# 12V_Buck_Motor.net
KiCad netlist of a schematic drawn in Altium Designer
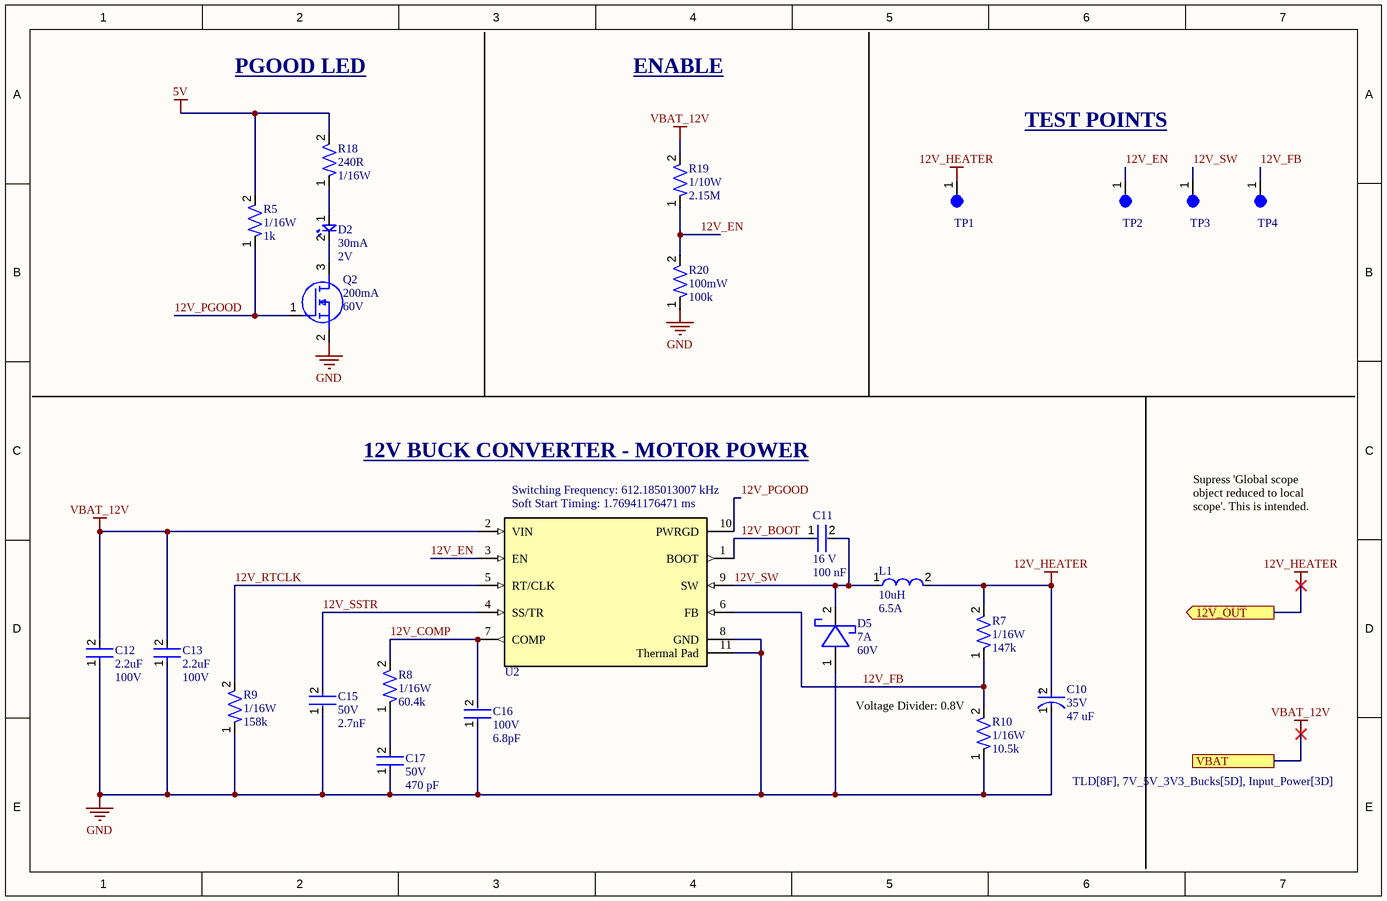
[diagram p0: 12V_Buck_Motor.SchDoc]

(export (version "E")
  (design (tool "Eeschema 10.0.6"))
  (components
    (comp (ref "C10")
      (value "EEH-ZC1V470P")
      (footprint "CAP-Radial-SMD")
      (description "CAP ALUM HYBRID 47UF 20% 35V SMD")
      (fields (field (name "VOLTAGE") "35V") (field (name "CAPACITANCE") "47 uF"))
      (libsource (lib "JLC_25") (part "CAP-47U-0002"))
    )
    (comp (ref "C11")
      (value "CC0402KRX7R7BB104")
      (footprint "CAP-0402")
      (description "CAP CER 0.1UF 16V X7R 0402")
      (fields (field (name "VOLTAGE RATING") "16 V") (field (name "CAPACITANCE") "100 nF"))
      (libsource (lib "JLC_25") (part "CAP-0.1U-0001"))
    )
    (comp (ref "C12")
      (value "CC1206KKX7R0BB225")
      (footprint "CAP-1206")
      (description "CAP CER 2.2UF 100V X7R 1206")
      (fields (field (name "CAPACITANCE") "2.2uF") (field (name "VOLTAGE") "100V"))
      (libsource (lib "JLC_25") (part "CAP-2.2U-0001"))
    )
    (comp (ref "C13")
      (value "CC1206KKX7R0BB225")
      (footprint "CAP-1206")
      (description "CAP CER 2.2UF 100V X7R 1206")
      (fields (field (name "CAPACITANCE") "2.2uF") (field (name "VOLTAGE") "100V"))
      (libsource (lib "JLC_25") (part "CAP-2.2U-0001"))
    )
    (comp (ref "C15")
      (value "GRM2165C1H272JA01D")
      (footprint "CAP-0805")
      (description "CAP CER 2700PF 50V C0G/NP0 0805")
      (fields (field (name "VOLTAGE") "50V") (field (name "CAPACITANCE") "2.7nF"))
      (libsource (lib "JLC_25") (part "CAP-2.7N-0001"))
    )
    (comp (ref "C16")
      (value "CC0603CRNPO0BN6R8")
      (footprint "CAP-0603")
      (description "CAP CER 6.8PF 100V C0G/NPO 0603")
      (fields (field (name "VOLTAGE") "100V") (field (name "CAPACITANCE") "6.8pF"))
      (libsource (lib "JLC_25") (part "CAP-6.8P-0001"))
    )
    (comp (ref "C17")
      (value "CC0805JRNPO9BN471")
      (footprint "CAP-0805")
      (description "CAP CER 470PF 50V C0G/NPO 0805")
      (fields (field (name "VOLTAGE") "50V") (field (name "CAPACITANCE") "470 pF"))
      (libsource (lib "JLC_25") (part "CAP-470P-0001"))
    )
    (comp (ref "D2")
      (value "BL-HKC36G-AV-TRB")
      (footprint "LED-0603")
      (description "LED YELLOW CLEAR 0603 SMD")
      (fields (field (name "FORWARD CURRENT") "30mA") (field (name "FORWARD VOLTAGE") "2V"))
      (libsource (lib "JLC_25") (part "LED-0001"))
    )
    (comp (ref "D5")
      (value "PDS760-13")
      (footprint "DO-POWERDI5")
      (description "DIODE SCHOTTKY 60V 7A POWERDI5")
      (fields (field (name "FORWARD CURRENT") "7A") (field (name "REVERSE VOLTAGE (DC)") "60V"))
      (libsource (lib "JLC_25") (part "DIO-SCHOTTKY-0001"))
    )
    (comp (ref "L1")
      (value "BMRF001010401R0MD1")
      (footprint "IND-10UH-0001")
      (description "FIXED IND 10UH 6.5A 30 MOHM SMD")
      (fields (field (name "INDUCTANCE") "10uH") (field (name "CURRENT RATING") "6.5A"))
      (libsource (lib "JLC_25") (part "IND-10U-0001"))
    )
    (comp (ref "Q2")
      (value "T2N7002AK,LM")
      (footprint "IC-SOT23-3")
      (description "MOSFET N-CH 60V 200MA SOT23")
      (fields (field (name "CONTINUOUS CURRENT") "200mA") (field (name "VOLTAGE") "60V"))
      (libsource (lib "JLC_25") (part "NMOS-200MA-0001"))
    )
    (comp (ref "R5")
      (value "RC0402FR-071KL")
      (footprint "RES-0402")
      (description "RES 1K OHM 1% 1/16W 0402")
      (fields (field (name "TOLERANCE") "1%") (field (name "POWER") "1/16W") (field (name "RESISTANCE") "1k"))
      (libsource (lib "JLC_25") (part "RES-1k-0001"))
    )
    (comp (ref "R7")
      (value "RC0402FR-07147KL")
      (footprint "RES-0402")
      (description "RES 147K OHM 1% 1/16W 0402")
      (fields
        (field (name "TOLERANCE") "1%")
        (field (name "POWER") "1/16W")
        (field (name "RESISTANCE") "147k")
      )
      (libsource (lib "JLC_25") (part "RES-147k-0001"))
    )
    (comp (ref "R8")
      (value "RC0402FR-0760K4L")
      (footprint "RES-0402")
      (description "RES 60.4K OHM 1% 1/16W 0402")
      (fields
        (field (name "TOLERANCE") "1%")
        (field (name "POWER") "1/16W")
        (field (name "RESISTANCE") "60.4k")
      )
      (libsource (lib "JLC_25") (part "RES-60.4k-0001"))
    )
    (comp (ref "R9")
      (value "RC0402FR-07158KL")
      (footprint "RES-0402")
      (description "RES 158K OHM 1% 1/16W 0402")
      (fields
        (field (name "TOLERANCE") "1%")
        (field (name "POWER") "1/16W")
        (field (name "RESISTANCE") "158k")
      )
      (libsource (lib "JLC_25") (part "RES-158k-0001"))
    )
    (comp (ref "R10")
      (value "RC0402FR-0710K5L")
      (footprint "RES-0402")
      (description "RES 10.5K OHM 1% 1/16W 0402")
      (fields
        (field (name "TOLERANCE") "1%")
        (field (name "POWER") "1/16W")
        (field (name "RESISTANCE") "10.5k")
      )
      (libsource (lib "JLC_25") (part "RES-10.5k-0001"))
    )
    (comp (ref "R18")
      (value "RC0402FR-07240RL")
      (footprint "RES-0402")
      (description "240R 0.063W 1% 0402 (1005 Metric)  SMD")
      (fields
        (field (name "TOLERANCE") "1%")
        (field (name "RESISTANCE") "240R")
        (field (name "POWER") "1/16W")
      )
      (libsource (lib "JLC_25") (part "RES-240-0001"))
    )
    (comp (ref "R19")
      (value "RC0603FR-072M15L")
      (footprint "RES-0603")
      (description "RES SMD 2.15M OHM 1% 1/10W 0603")
      (fields
        (field (name "TOLERANCE") "1%")
        (field (name "POWER") "1/10W")
        (field (name "RESISTANCE") "2.15M")
      )
      (libsource (lib "JLC_25") (part "RES-2.15M-0001"))
    )
    (comp (ref "R20")
      (value "RC0603FR-07100KL")
      (footprint "RES-0603")
      (description "RES SMD 100K OHM 1% 1/10W 0603")
      (fields
        (field (name "TOLERANCE") "1%")
        (field (name "POWER") "100mW")
        (field (name "RESISTANCE") "100k")
      )
      (libsource (lib "JLC_25") (part "RES-100k-0001"))
    )
    (comp (ref "TP1")
      (value "5003")
      (footprint "TEST-POINT-0001")
      (description "Oranange PC Test Point, Miniature Phoisphor Bronze Silver Plating Through Hole Mounting Type")
      (libsource (lib "JLC_25") (part "TEST-POINT-0001"))
    )
    (comp (ref "TP2")
      (value "5003")
      (footprint "TEST-POINT-0001")
      (description "Oranange PC Test Point, Miniature Phoisphor Bronze Silver Plating Through Hole Mounting Type")
      (libsource (lib "JLC_25") (part "TEST-POINT-0001"))
    )
    (comp (ref "TP3")
      (value "5003")
      (footprint "TEST-POINT-0001")
      (description "Oranange PC Test Point, Miniature Phoisphor Bronze Silver Plating Through Hole Mounting Type")
      (libsource (lib "JLC_25") (part "TEST-POINT-0001"))
    )
    (comp (ref "TP4")
      (value "5003")
      (footprint "TEST-POINT-0001")
      (description "Oranange PC Test Point, Miniature Phoisphor Bronze Silver Plating Through Hole Mounting Type")
      (libsource (lib "JLC_25") (part "TEST-POINT-0001"))
    )
    (comp (ref "U2")
      (value "TPS54561DPRR")
      (footprint "IC-10WSON")
      (description "IC REG BUCK ADJ 5A 10WSON")
      (libsource (lib "JLC_25") (part "IC-BUCK-0001"))
    )
  )
  (nets
    (net (code "1") (name "/12V_BOOT") (class "Default")
      (node (ref "C11") (pin "1") (pinfunction "1_1") (pintype "passive"))
      (node (ref "U2") (pin "1") (pinfunction "BOOT_1") (pintype "output"))
    )
    (net (code "2") (name "/12V_COMP") (class "Default")
      (node (ref "C16") (pin "2") (pinfunction "2_2") (pintype "passive"))
      (node (ref "R8") (pin "2") (pinfunction "2_2") (pintype "passive"))
      (node (ref "U2") (pin "7") (pinfunction "COMP_7") (pintype "output"))
    )
    (net (code "3") (name "/12V_EN") (class "Default")
      (node (ref "R19") (pin "1") (pinfunction "1_1") (pintype "passive"))
      (node (ref "R20") (pin "2") (pinfunction "2_2") (pintype "passive"))
      (node (ref "TP2") (pin "1") (pinfunction "0_1") (pintype "passive"))
      (node (ref "U2") (pin "3") (pinfunction "EN_3") (pintype "input"))
    )
    (net (code "4") (name "/12V_FB") (class "Default")
      (node (ref "R10") (pin "2") (pinfunction "2_2") (pintype "passive"))
      (node (ref "R7") (pin "1") (pinfunction "1_1") (pintype "passive"))
      (node (ref "TP4") (pin "1") (pinfunction "0_1") (pintype "passive"))
      (node (ref "U2") (pin "6") (pinfunction "FB_6") (pintype "input"))
    )
    (net (code "5") (name "/12V_PGOOD") (class "Default")
      (node (ref "Q2") (pin "1") (pinfunction "G_1") (pintype "passive"))
      (node (ref "R5") (pin "1") (pinfunction "1_1") (pintype "passive"))
      (node (ref "U2") (pin "10") (pinfunction "PWRGD_10") (pintype "open_collector"))
    )
    (net (code "6") (name "/12V_RTCLK") (class "Default")
      (node (ref "R9") (pin "2") (pinfunction "2_2") (pintype "passive"))
      (node (ref "U2") (pin "5") (pinfunction "RT/CLK_5") (pintype "input"))
    )
    (net (code "7") (name "/12V_SSTR") (class "Default")
      (node (ref "C15") (pin "2") (pinfunction "2_2") (pintype "passive"))
      (node (ref "U2") (pin "4") (pinfunction "SS/TR_4") (pintype "input"))
    )
    (net (code "8") (name "/12V_SW") (class "Default")
      (node (ref "C11") (pin "2") (pinfunction "2_2") (pintype "passive"))
      (node (ref "D5") (pin "2") (pinfunction "ANODE_2") (pintype "passive"))
      (node (ref "L1") (pin "1") (pinfunction "1_1") (pintype "passive"))
      (node (ref "TP3") (pin "1") (pinfunction "0_1") (pintype "passive"))
      (node (ref "U2") (pin "9") (pinfunction "SW_9") (pintype "input"))
    )
    (net (code "9") (name "5V") (class "Default")
      (node (ref "R18") (pin "2") (pinfunction "2_2") (pintype "passive"))
      (node (ref "R5") (pin "2") (pinfunction "2_2") (pintype "passive"))
    )
    (net (code "10") (name "12V_HEATER") (class "Default")
      (node (ref "C10") (pin "2") (pinfunction "A_2") (pintype "passive"))
      (node (ref "L1") (pin "2") (pinfunction "2_2") (pintype "passive"))
      (node (ref "R7") (pin "2") (pinfunction "2_2") (pintype "passive"))
      (node (ref "TP1") (pin "1") (pinfunction "0_1") (pintype "passive"))
    )
    (net (code "11") (name "GND") (class "Default")
      (node (ref "C10") (pin "1") (pinfunction "C_1") (pintype "passive"))
      (node (ref "C12") (pin "1") (pinfunction "1_1") (pintype "passive"))
      (node (ref "C13") (pin "1") (pinfunction "1_1") (pintype "passive"))
      (node (ref "C15") (pin "1") (pinfunction "1_1") (pintype "passive"))
      (node (ref "C16") (pin "1") (pinfunction "1_1") (pintype "passive"))
      (node (ref "C17") (pin "1") (pinfunction "1_1") (pintype "passive"))
      (node (ref "D5") (pin "1") (pinfunction "CATHODE_1") (pintype "passive"))
      (node (ref "Q2") (pin "2") (pinfunction "S_2") (pintype "passive"))
      (node (ref "R10") (pin "1") (pinfunction "1_1") (pintype "passive"))
      (node (ref "R20") (pin "1") (pinfunction "1_1") (pintype "passive"))
      (node (ref "R9") (pin "1") (pinfunction "1_1") (pintype "passive"))
      (node (ref "U2") (pin "11") (pinfunction "Thermal_Pad_11") (pintype "power_in"))
      (node (ref "U2") (pin "8") (pinfunction "GND_8") (pintype "power_in"))
    )
    (net (code "12") (name "Net-(C17-Pad2)") (class "Default")
      (node (ref "C17") (pin "2") (pinfunction "2_2") (pintype "passive"))
      (node (ref "R8") (pin "1") (pinfunction "1_1") (pintype "passive"))
    )
    (net (code "13") (name "Net-(D2-Pad1)") (class "Default")
      (node (ref "D2") (pin "1") (pinfunction "1_1") (pintype "passive"))
      (node (ref "R18") (pin "1") (pinfunction "1_1") (pintype "passive"))
    )
    (net (code "14") (name "Net-(Q2-D)") (class "Default")
      (node (ref "D2") (pin "2") (pinfunction "2_2") (pintype "passive"))
      (node (ref "Q2") (pin "3") (pinfunction "D_3") (pintype "passive"))
    )
    (net (code "15") (name "VBAT_12V") (class "Default")
      (node (ref "C12") (pin "2") (pinfunction "2_2") (pintype "passive"))
      (node (ref "C13") (pin "2") (pinfunction "2_2") (pintype "passive"))
      (node (ref "R19") (pin "2") (pinfunction "2_2") (pintype "passive"))
      (node (ref "U2") (pin "2") (pinfunction "VIN_2") (pintype "input"))
    )
  )
)
